# ubadge.net
KiCad netlist of a schematic drawn in EAGLE
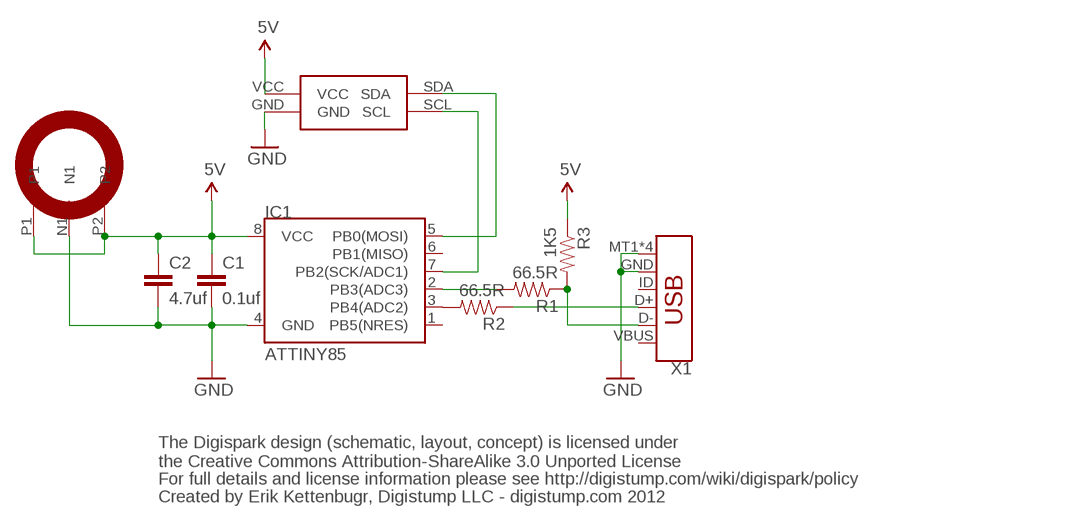
[diagram p0: schematic, sheet 1]

(export (version "E")
  (design (tool "Eeschema 10.0.6"))
  (components
    (comp (ref "C1")
      (value "0.1uf")
      (footprint "eagle-import:0402-CAP")
      (libsource (lib "eagle-import") (part "CAP0402-CAP"))
    )
    (comp (ref "C2")
      (value "4.7uf")
      (footprint "eagle-import:0805")
      (libsource (lib "eagle-import") (part "CAP0805"))
    )
    (comp (ref "IC1")
      (value "ATTINY85")
      (footprint "eagle-import:SO08-EIAJ")
      (libsource (lib "eagle-import") (part "ATTINY45"))
    )
    (comp (ref "R1")
      (value "66.5R")
      (footprint "eagle-import:0402-RES")
      (libsource (lib "eagle-import") (part "RESISTOR0402-RES"))
    )
    (comp (ref "R2")
      (value "66.5R")
      (footprint "eagle-import:0402-RES")
      (libsource (lib "eagle-import") (part "RESISTOR0402-RES"))
    )
    (comp (ref "R3")
      (value "1K5")
      (footprint "eagle-import:0402-RES")
      (libsource (lib "eagle-import") (part "RESISTOR0402-RES"))
    )
    (comp (ref "U$1")
      (value "SAO-SMT-BOARD")
      (footprint "eagle-import:SAO-SMD-BADGE-SOCKET")
      (libsource (lib "eagle-import") (part "SAO-SMT-BOARD"))
    )
    (comp (ref "U$2")
      (value "CR2032-VERT")
      (footprint "eagle-import:CR2032-VERT")
      (libsource (lib "eagle-import") (part "CR2032-VERT"))
    )
    (comp (ref "X1")
      (value "USB_MICRO-B_SMT")
      (footprint "eagle-import:USB-MICROB")
      (libsource (lib "eagle-import") (part "USB_MICRO-B_SMT"))
    )
  )
  (nets
    (net (code "1") (name "/VBUS") (class "Default")
      (node (ref "X1") (pin "VBUS") (pinfunction "VBUS_VBUS") (pintype "power_in"))
    )
    (net (code "2") (name "5V") (class "Default")
      (node (ref "C1") (pin "1") (pinfunction "1_1") (pintype "passive"))
      (node (ref "C2") (pin "1") (pinfunction "1_1") (pintype "passive"))
      (node (ref "IC1") (pin "8") (pinfunction "VCC_8") (pintype "bidirectional"))
      (node (ref "R3") (pin "1") (pinfunction "1_1") (pintype "passive"))
      (node (ref "U$1") (pin "VCC") (pinfunction "VCC_VCC") (pintype "bidirectional"))
      (node (ref "U$2") (pin "P1") (pinfunction "P1_P1") (pintype "bidirectional"))
      (node (ref "U$2") (pin "P2") (pinfunction "P2_P2") (pintype "bidirectional"))
    )
    (net (code "3") (name "GND") (class "Default")
      (node (ref "C1") (pin "2") (pinfunction "2_2") (pintype "passive"))
      (node (ref "C2") (pin "2") (pinfunction "2_2") (pintype "passive"))
      (node (ref "IC1") (pin "4") (pinfunction "GND_4") (pintype "bidirectional"))
      (node (ref "U$1") (pin "GND") (pinfunction "GND_GND") (pintype "bidirectional"))
      (node (ref "U$2") (pin "N1") (pinfunction "N1_N1") (pintype "bidirectional"))
      (node (ref "X1") (pin "GND") (pinfunction "GND_GND") (pintype "power_in"))
      (node (ref "X1") (pin "MT1") (pinfunction "SHIELD_MT1") (pintype "bidirectional"))
      (node (ref "X1") (pin "MT2") (pinfunction "SHIELD_MT2") (pintype "bidirectional"))
      (node (ref "X1") (pin "P$1") (pinfunction "SHIELD_P$1") (pintype "bidirectional"))
      (node (ref "X1") (pin "P$2") (pinfunction "SHIELD_P$2") (pintype "bidirectional"))
    )
    (net (code "4") (name "Net-(IC1-PB0(MOSI))") (class "Default")
      (node (ref "IC1") (pin "5") (pinfunction "PB0(MOSI)_5") (pintype "bidirectional"))
      (node (ref "U$1") (pin "SDA") (pinfunction "SDA_SDA") (pintype "bidirectional"))
    )
    (net (code "5") (name "Net-(IC1-PB2(SCK{slash}ADC1))") (class "Default")
      (node (ref "IC1") (pin "7") (pinfunction "PB2(SCK/ADC1)_7") (pintype "bidirectional"))
      (node (ref "U$1") (pin "SCL") (pinfunction "SCL_SCL") (pintype "bidirectional"))
    )
    (net (code "6") (name "Net-(IC1-PB3(ADC3))") (class "Default")
      (node (ref "IC1") (pin "2") (pinfunction "PB3(ADC3)_2") (pintype "bidirectional"))
      (node (ref "R1") (pin "2") (pinfunction "2_2") (pintype "passive"))
    )
    (net (code "7") (name "Net-(IC1-PB4(ADC2))") (class "Default")
      (node (ref "IC1") (pin "3") (pinfunction "PB4(ADC2)_3") (pintype "bidirectional"))
      (node (ref "R2") (pin "2") (pinfunction "2_2") (pintype "passive"))
    )
    (net (code "8") (name "Net-(R1-Pad1)") (class "Default")
      (node (ref "R1") (pin "1") (pinfunction "1_1") (pintype "passive"))
      (node (ref "R3") (pin "2") (pinfunction "2_2") (pintype "passive"))
      (node (ref "X1") (pin "D-") (pinfunction "D-_D-") (pintype "bidirectional"))
    )
    (net (code "9") (name "Net-(R2-Pad1)") (class "Default")
      (node (ref "R2") (pin "1") (pinfunction "1_1") (pintype "passive"))
      (node (ref "X1") (pin "D+") (pinfunction "D+_D+") (pintype "bidirectional"))
    )
    (net (code "10") (name "unconnected-(IC1-PB1(MISO)-Pad6)") (class "Default")
      (node (ref "IC1") (pin "6") (pinfunction "PB1(MISO)_6") (pintype "bidirectional"))
    )
    (net (code "11") (name "unconnected-(IC1-PB5(NRES)-Pad1)") (class "Default")
      (node (ref "IC1") (pin "1") (pinfunction "PB5(NRES)_1") (pintype "bidirectional"))
    )
    (net (code "12") (name "unconnected-(X1-PadID)") (class "Default")
      (node (ref "X1") (pin "ID") (pinfunction "ID_ID") (pintype "bidirectional"))
    )
  )
)
